# LedDriverBreakout.net
KiCad netlist of a schematic drawn in EAGLE
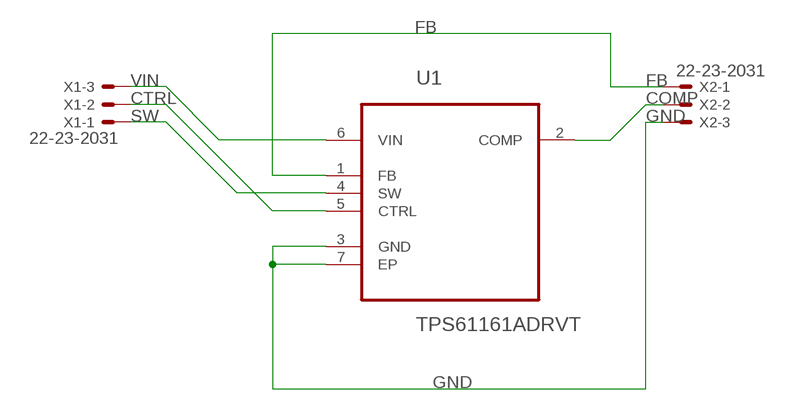
[diagram p0: schematic, sheet 1]

(export (version "E")
  (design (tool "Eeschema 10.0.6"))
  (components
    (comp (ref "U1")
      (value "TPS61161ADRVT")
      (footprint "eagle-import:SON65P200X200X80-7N")
      (libsource (lib "eagle-import") (part "TPS61161ADRVT"))
    )
    (comp (ref "X1")
      (value "22-23-2031")
      (footprint "eagle-import:22-23-2031")
      (fields (field (name "MF") "MOLEX"))
      (libsource (lib "eagle-import") (part "22-23-2031"))
    )
    (comp (ref "X2")
      (value "22-23-2031")
      (footprint "eagle-import:22-23-2031")
      (fields (field (name "MF") "MOLEX"))
      (libsource (lib "eagle-import") (part "22-23-2031"))
    )
  )
  (nets
    (net (code "1") (name "/COMP") (class "Default")
      (node (ref "U1") (pin "2") (pinfunction "COMP_2") (pintype "output"))
      (node (ref "X2") (pin "2") (pinfunction "S_2") (pintype "passive"))
    )
    (net (code "2") (name "/CTRL") (class "Default")
      (node (ref "U1") (pin "5") (pinfunction "CTRL_5") (pintype "input"))
      (node (ref "X1") (pin "2") (pinfunction "S_2") (pintype "passive"))
    )
    (net (code "3") (name "/FB") (class "Default")
      (node (ref "U1") (pin "1") (pinfunction "FB_1") (pintype "input"))
      (node (ref "X2") (pin "1") (pinfunction "S_1") (pintype "passive"))
    )
    (net (code "4") (name "/GND") (class "Default")
      (node (ref "U1") (pin "3") (pinfunction "GND_3") (pintype "passive"))
      (node (ref "U1") (pin "7") (pinfunction "EP_7") (pintype "passive"))
      (node (ref "X2") (pin "3") (pinfunction "S_3") (pintype "passive"))
    )
    (net (code "5") (name "/SW") (class "Default")
      (node (ref "U1") (pin "4") (pinfunction "SW_4") (pintype "input"))
      (node (ref "X1") (pin "1") (pinfunction "S_1") (pintype "passive"))
    )
    (net (code "6") (name "/VIN") (class "Default")
      (node (ref "U1") (pin "6") (pinfunction "VIN_6") (pintype "power_in"))
      (node (ref "X1") (pin "3") (pinfunction "S_3") (pintype "passive"))
    )
  )
)
